# Power.net
KiCad netlist of a schematic drawn in Altium Designer
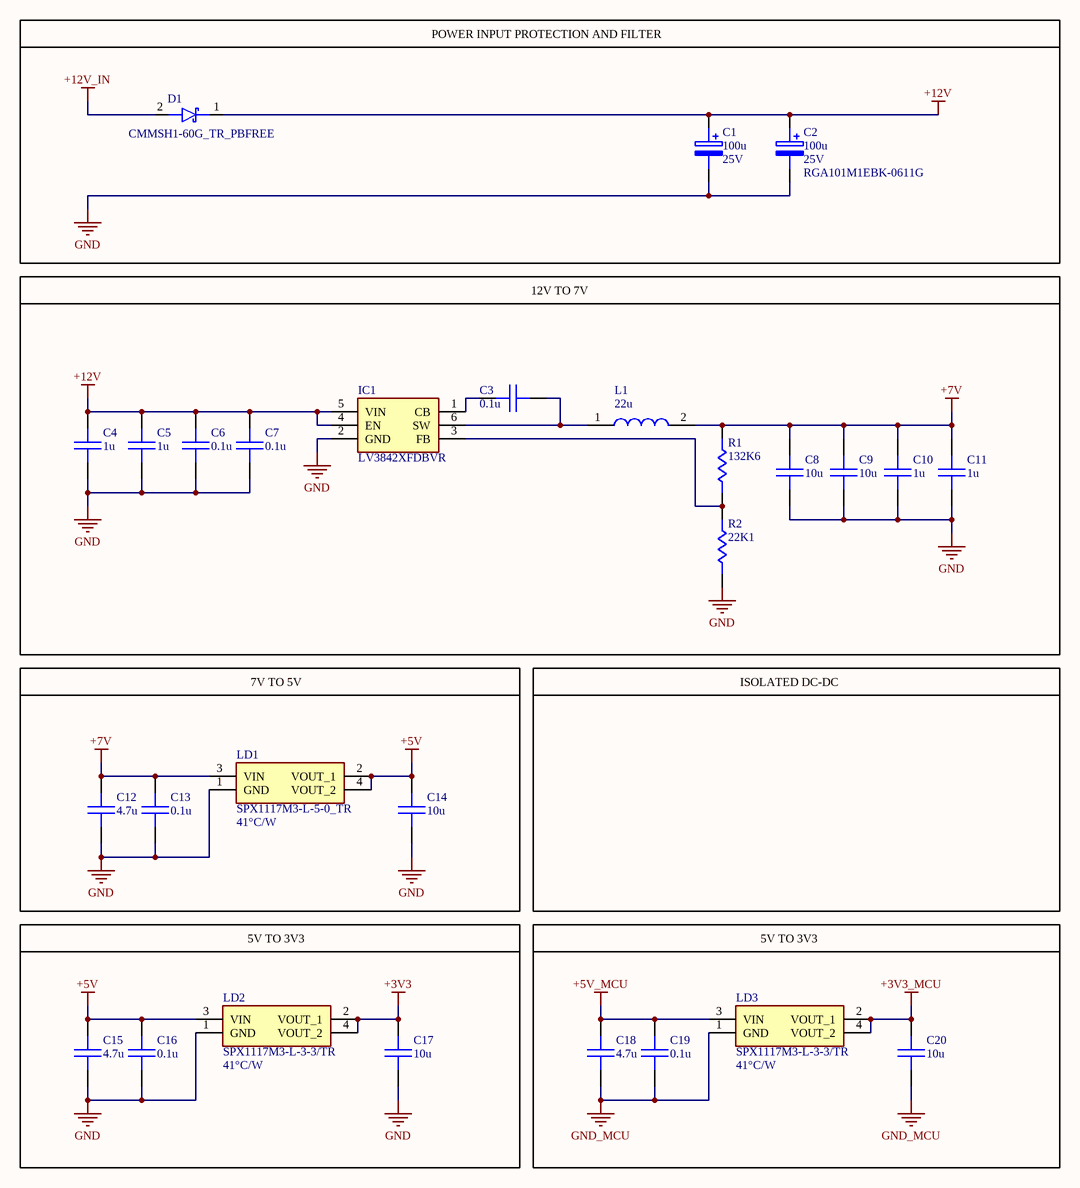
[diagram p0: Power.SchDoc]

(export (version "E")
  (design (tool "Eeschema 10.0.6"))
  (components
    (comp (ref "C1")
      (value "100u")
      (footprint "C_THT_6.3X11X2.5")
      (description "Aluminium Electrolytic Capacitors - Radial Leaded 25V 100uF 105C 6.3x11mm")
      (fields (field (name "VOLTAGE") "25V") (field (name "Comment") "RGA101M1EBK-0611G"))
      (libsource (lib "My_Integrated_Lib") (part "CAP_POL_THT_100u_25V"))
    )
    (comp (ref "C2")
      (value "RGA101M1EBK-0611G")
      (footprint "C_THT_6.3X11X2.5")
      (description "Aluminium Electrolytic Capacitors - Radial Leaded 25V 100uF 105C 6.3x11mm")
      (fields (field (name "ALTIUM_VALUE") "100u") (field (name "VOLTAGE") "25V"))
      (libsource (lib "My_Integrated_Lib") (part "CAP_POL_THT_100u_25V"))
    )
    (comp (ref "C3")
      (value "0.1u")
      (footprint "C_0603")
      (description "SMD Chip Capacitor")
      (libsource (lib "My_Integrated_Lib") (part "CAP"))
    )
    (comp (ref "C4")
      (value "1u")
      (footprint "C_0805")
      (description "SMD Chip Capacitor")
      (libsource (lib "My_Integrated_Lib") (part "CAP"))
    )
    (comp (ref "C5")
      (value "1u")
      (footprint "C_0805")
      (description "SMD Chip Capacitor")
      (libsource (lib "My_Integrated_Lib") (part "CAP"))
    )
    (comp (ref "C6")
      (value "0.1u")
      (footprint "C_0603")
      (description "SMD Chip Capacitor")
      (libsource (lib "My_Integrated_Lib") (part "CAP"))
    )
    (comp (ref "C7")
      (value "0.1u")
      (footprint "C_0603")
      (description "SMD Chip Capacitor")
      (libsource (lib "My_Integrated_Lib") (part "CAP"))
    )
    (comp (ref "C8")
      (value "10u")
      (footprint "C_1206")
      (description "SMD Chip Capacitor")
      (libsource (lib "My_Integrated_Lib") (part "CAP"))
    )
    (comp (ref "C9")
      (value "10u")
      (footprint "C_1206")
      (description "SMD Chip Capacitor")
      (libsource (lib "My_Integrated_Lib") (part "CAP"))
    )
    (comp (ref "C10")
      (value "1u")
      (footprint "C_0805")
      (description "SMD Chip Capacitor")
      (libsource (lib "My_Integrated_Lib") (part "CAP"))
    )
    (comp (ref "C11")
      (value "1u")
      (footprint "C_0805")
      (description "SMD Chip Capacitor")
      (libsource (lib "My_Integrated_Lib") (part "CAP"))
    )
    (comp (ref "C12")
      (value "4.7u")
      (footprint "C_0805")
      (description "SMD Chip Capacitor")
      (libsource (lib "My_Integrated_Lib") (part "CAP"))
    )
    (comp (ref "C13")
      (value "0.1u")
      (footprint "C_0603")
      (description "SMD Chip Capacitor")
      (libsource (lib "My_Integrated_Lib") (part "CAP"))
    )
    (comp (ref "C14")
      (value "10u")
      (footprint "C_1206")
      (description "SMD Chip Capacitor")
      (libsource (lib "My_Integrated_Lib") (part "CAP"))
    )
    (comp (ref "C15")
      (value "4.7u")
      (footprint "C_0805")
      (description "SMD Chip Capacitor")
      (libsource (lib "My_Integrated_Lib") (part "CAP"))
    )
    (comp (ref "C16")
      (value "0.1u")
      (footprint "C_0603")
      (description "SMD Chip Capacitor")
      (libsource (lib "My_Integrated_Lib") (part "CAP"))
    )
    (comp (ref "C17")
      (value "10u")
      (footprint "C_1206")
      (description "SMD Chip Capacitor")
      (libsource (lib "My_Integrated_Lib") (part "CAP"))
    )
    (comp (ref "C18")
      (value "4.7u")
      (footprint "C_0805")
      (description "SMD Chip Capacitor")
      (libsource (lib "My_Integrated_Lib") (part "CAP"))
    )
    (comp (ref "C19")
      (value "0.1u")
      (footprint "C_0603")
      (description "SMD Chip Capacitor")
      (libsource (lib "My_Integrated_Lib") (part "CAP"))
    )
    (comp (ref "C20")
      (value "10u")
      (footprint "C_1206")
      (description "SMD Chip Capacitor")
      (libsource (lib "My_Integrated_Lib") (part "CAP"))
    )
    (comp (ref "D1")
      (value "CMMSH1-60G_TR_PBFREE")
      (footprint "SOD-123-2")
      (description "Schottky Diodes & Rectifiers")
      (libsource (lib "My_Integrated_Lib") (part "DIODE_SCHOTTKY_CMMSH1-60G_TR_PBFREE"))
    )
    (comp (ref "IC1")
      (value "LV3842XFDBVR")
      (footprint "SOT23-6")
      (description "Switching Voltage Regulators 4-V to 36-V 600-mA synchronous step-dow (FPWM)")
      (libsource (lib "My_Integrated_Lib") (part "DC_DC_LV3842XFDBVR"))
    )
    (comp (ref "L1")
      (value "22u")
      (footprint "IND_5x5x4.5")
      (description "VLS5045EX-220M")
      (libsource (lib "My_Integrated_Lib") (part "INDUCTOR"))
    )
    (comp (ref "LD1")
      (value "SPX1117M3-L-5-0_TR")
      (footprint "SOT223-3")
      (description "LDO Voltage Regulators, 800mA, 5V Fixed Output")
      (fields (field (name "JUNCTION TO AMBIENT") "41°C/W"))
      (libsource (lib "My_Integrated_Lib") (part "LDO_SPX1117M3-L-5-0_TR"))
    )
    (comp (ref "LD2")
      (value "SPX1117M3-L-3-3/TR")
      (footprint "SOT223-3")
      (description "LDO Voltage Regulators, 800mA, 3.3V Fixed Output")
      (fields (field (name "JUNCTION TO AMBIENT") "41°C/W"))
      (libsource (lib "My_Integrated_Lib") (part "LDO_SPX1117M3-L-3-3/TR"))
    )
    (comp (ref "LD3")
      (value "SPX1117M3-L-3-3/TR")
      (footprint "SOT223-3")
      (description "LDO Voltage Regulators, 800mA, 3.3V Fixed Output")
      (fields (field (name "JUNCTION TO AMBIENT") "41°C/W"))
      (libsource (lib "My_Integrated_Lib") (part "LDO_SPX1117M3-L-3-3/TR"))
    )
    (comp (ref "R1")
      (value "132K6")
      (footprint "R_0603")
      (description "SMD Chip Resistor")
      (libsource (lib "My_Integrated_Lib") (part "RES"))
    )
    (comp (ref "R2")
      (value "22K1")
      (footprint "R_0603")
      (description "SMD Chip Resistor")
      (libsource (lib "My_Integrated_Lib") (part "RES"))
    )
  )
  (nets
    (net (code "1") (name "+3V3") (class "Default")
      (node (ref "C17") (pin "1") (pinfunction "1_1") (pintype "passive"))
      (node (ref "LD2") (pin "2") (pinfunction "VOUT_1_2") (pintype "passive"))
      (node (ref "LD2") (pin "4") (pinfunction "VOUT_2_4") (pintype "passive"))
    )
    (net (code "2") (name "+3V3_MCU") (class "Default")
      (node (ref "C20") (pin "1") (pinfunction "1_1") (pintype "passive"))
      (node (ref "LD3") (pin "2") (pinfunction "VOUT_1_2") (pintype "passive"))
      (node (ref "LD3") (pin "4") (pinfunction "VOUT_2_4") (pintype "passive"))
    )
    (net (code "3") (name "+5V") (class "Default")
      (node (ref "C14") (pin "1") (pinfunction "1_1") (pintype "passive"))
      (node (ref "C15") (pin "1") (pinfunction "1_1") (pintype "passive"))
      (node (ref "C16") (pin "1") (pinfunction "1_1") (pintype "passive"))
      (node (ref "LD1") (pin "2") (pinfunction "VOUT_1_2") (pintype "passive"))
      (node (ref "LD1") (pin "4") (pinfunction "VOUT_2_4") (pintype "passive"))
      (node (ref "LD2") (pin "3") (pinfunction "VIN_3") (pintype "passive"))
    )
    (net (code "4") (name "+5V_MCU") (class "Default")
      (node (ref "C18") (pin "1") (pinfunction "1_1") (pintype "passive"))
      (node (ref "C19") (pin "1") (pinfunction "1_1") (pintype "passive"))
      (node (ref "LD3") (pin "3") (pinfunction "VIN_3") (pintype "passive"))
    )
    (net (code "5") (name "+7V") (class "Default")
      (node (ref "C10") (pin "1") (pinfunction "1_1") (pintype "passive"))
      (node (ref "C11") (pin "1") (pinfunction "1_1") (pintype "passive"))
      (node (ref "C12") (pin "1") (pinfunction "1_1") (pintype "passive"))
      (node (ref "C13") (pin "1") (pinfunction "1_1") (pintype "passive"))
      (node (ref "C8") (pin "1") (pinfunction "1_1") (pintype "passive"))
      (node (ref "C9") (pin "1") (pinfunction "1_1") (pintype "passive"))
      (node (ref "L1") (pin "2") (pinfunction "2_2") (pintype "passive"))
      (node (ref "LD1") (pin "3") (pinfunction "VIN_3") (pintype "passive"))
      (node (ref "R1") (pin "2") (pinfunction "2_2") (pintype "passive"))
    )
    (net (code "6") (name "+12V") (class "Default")
      (node (ref "C1") (pin "1") (pinfunction "+_1") (pintype "passive"))
      (node (ref "C2") (pin "1") (pinfunction "+_1") (pintype "passive"))
      (node (ref "C4") (pin "1") (pinfunction "1_1") (pintype "passive"))
      (node (ref "C5") (pin "1") (pinfunction "1_1") (pintype "passive"))
      (node (ref "C6") (pin "2") (pinfunction "2_2") (pintype "passive"))
      (node (ref "C7") (pin "2") (pinfunction "2_2") (pintype "passive"))
      (node (ref "D1") (pin "1") (pinfunction "K_1") (pintype "passive"))
      (node (ref "IC1") (pin "4") (pinfunction "EN_4") (pintype "passive"))
      (node (ref "IC1") (pin "5") (pinfunction "VIN_5") (pintype "power_in"))
    )
    (net (code "7") (name "+12V_IN") (class "Default")
      (node (ref "D1") (pin "2") (pinfunction "A_2") (pintype "passive"))
    )
    (net (code "8") (name "GND") (class "Default")
      (node (ref "C1") (pin "2") (pinfunction "-_2") (pintype "passive"))
      (node (ref "C10") (pin "2") (pinfunction "2_2") (pintype "passive"))
      (node (ref "C11") (pin "2") (pinfunction "2_2") (pintype "passive"))
      (node (ref "C12") (pin "2") (pinfunction "2_2") (pintype "passive"))
      (node (ref "C13") (pin "2") (pinfunction "2_2") (pintype "passive"))
      (node (ref "C14") (pin "2") (pinfunction "2_2") (pintype "passive"))
      (node (ref "C15") (pin "2") (pinfunction "2_2") (pintype "passive"))
      (node (ref "C16") (pin "2") (pinfunction "2_2") (pintype "passive"))
      (node (ref "C17") (pin "2") (pinfunction "2_2") (pintype "passive"))
      (node (ref "C2") (pin "2") (pinfunction "-_2") (pintype "passive"))
      (node (ref "C4") (pin "2") (pinfunction "2_2") (pintype "passive"))
      (node (ref "C5") (pin "2") (pinfunction "2_2") (pintype "passive"))
      (node (ref "C6") (pin "1") (pinfunction "1_1") (pintype "passive"))
      (node (ref "C7") (pin "1") (pinfunction "1_1") (pintype "passive"))
      (node (ref "C8") (pin "2") (pinfunction "2_2") (pintype "passive"))
      (node (ref "C9") (pin "2") (pinfunction "2_2") (pintype "passive"))
      (node (ref "IC1") (pin "2") (pinfunction "GND_2") (pintype "power_in"))
      (node (ref "LD1") (pin "1") (pinfunction "GND_1") (pintype "passive"))
      (node (ref "LD2") (pin "1") (pinfunction "GND_1") (pintype "passive"))
      (node (ref "R2") (pin "1") (pinfunction "1_1") (pintype "passive"))
    )
    (net (code "9") (name "GND_MCU") (class "Default")
      (node (ref "C18") (pin "2") (pinfunction "2_2") (pintype "passive"))
      (node (ref "C19") (pin "2") (pinfunction "2_2") (pintype "passive"))
      (node (ref "C20") (pin "2") (pinfunction "2_2") (pintype "passive"))
      (node (ref "LD3") (pin "1") (pinfunction "GND_1") (pintype "passive"))
    )
    (net (code "10") (name "Net-(IC1-CB)") (class "Default")
      (node (ref "C3") (pin "2") (pinfunction "2_2") (pintype "passive"))
      (node (ref "IC1") (pin "1") (pinfunction "CB_1") (pintype "power_in"))
    )
    (net (code "11") (name "Net-(IC1-FB)") (class "Default")
      (node (ref "IC1") (pin "3") (pinfunction "FB_3") (pintype "passive"))
      (node (ref "R1") (pin "1") (pinfunction "1_1") (pintype "passive"))
      (node (ref "R2") (pin "2") (pinfunction "2_2") (pintype "passive"))
    )
    (net (code "12") (name "Net-(IC1-SW)") (class "Default")
      (node (ref "C3") (pin "1") (pinfunction "1_1") (pintype "passive"))
      (node (ref "IC1") (pin "6") (pinfunction "SW_6") (pintype "power_in"))
      (node (ref "L1") (pin "1") (pinfunction "1_1") (pintype "passive"))
    )
  )
)
